# ESCapemk2.net
KiCad netlist of a schematic drawn in EAGLE
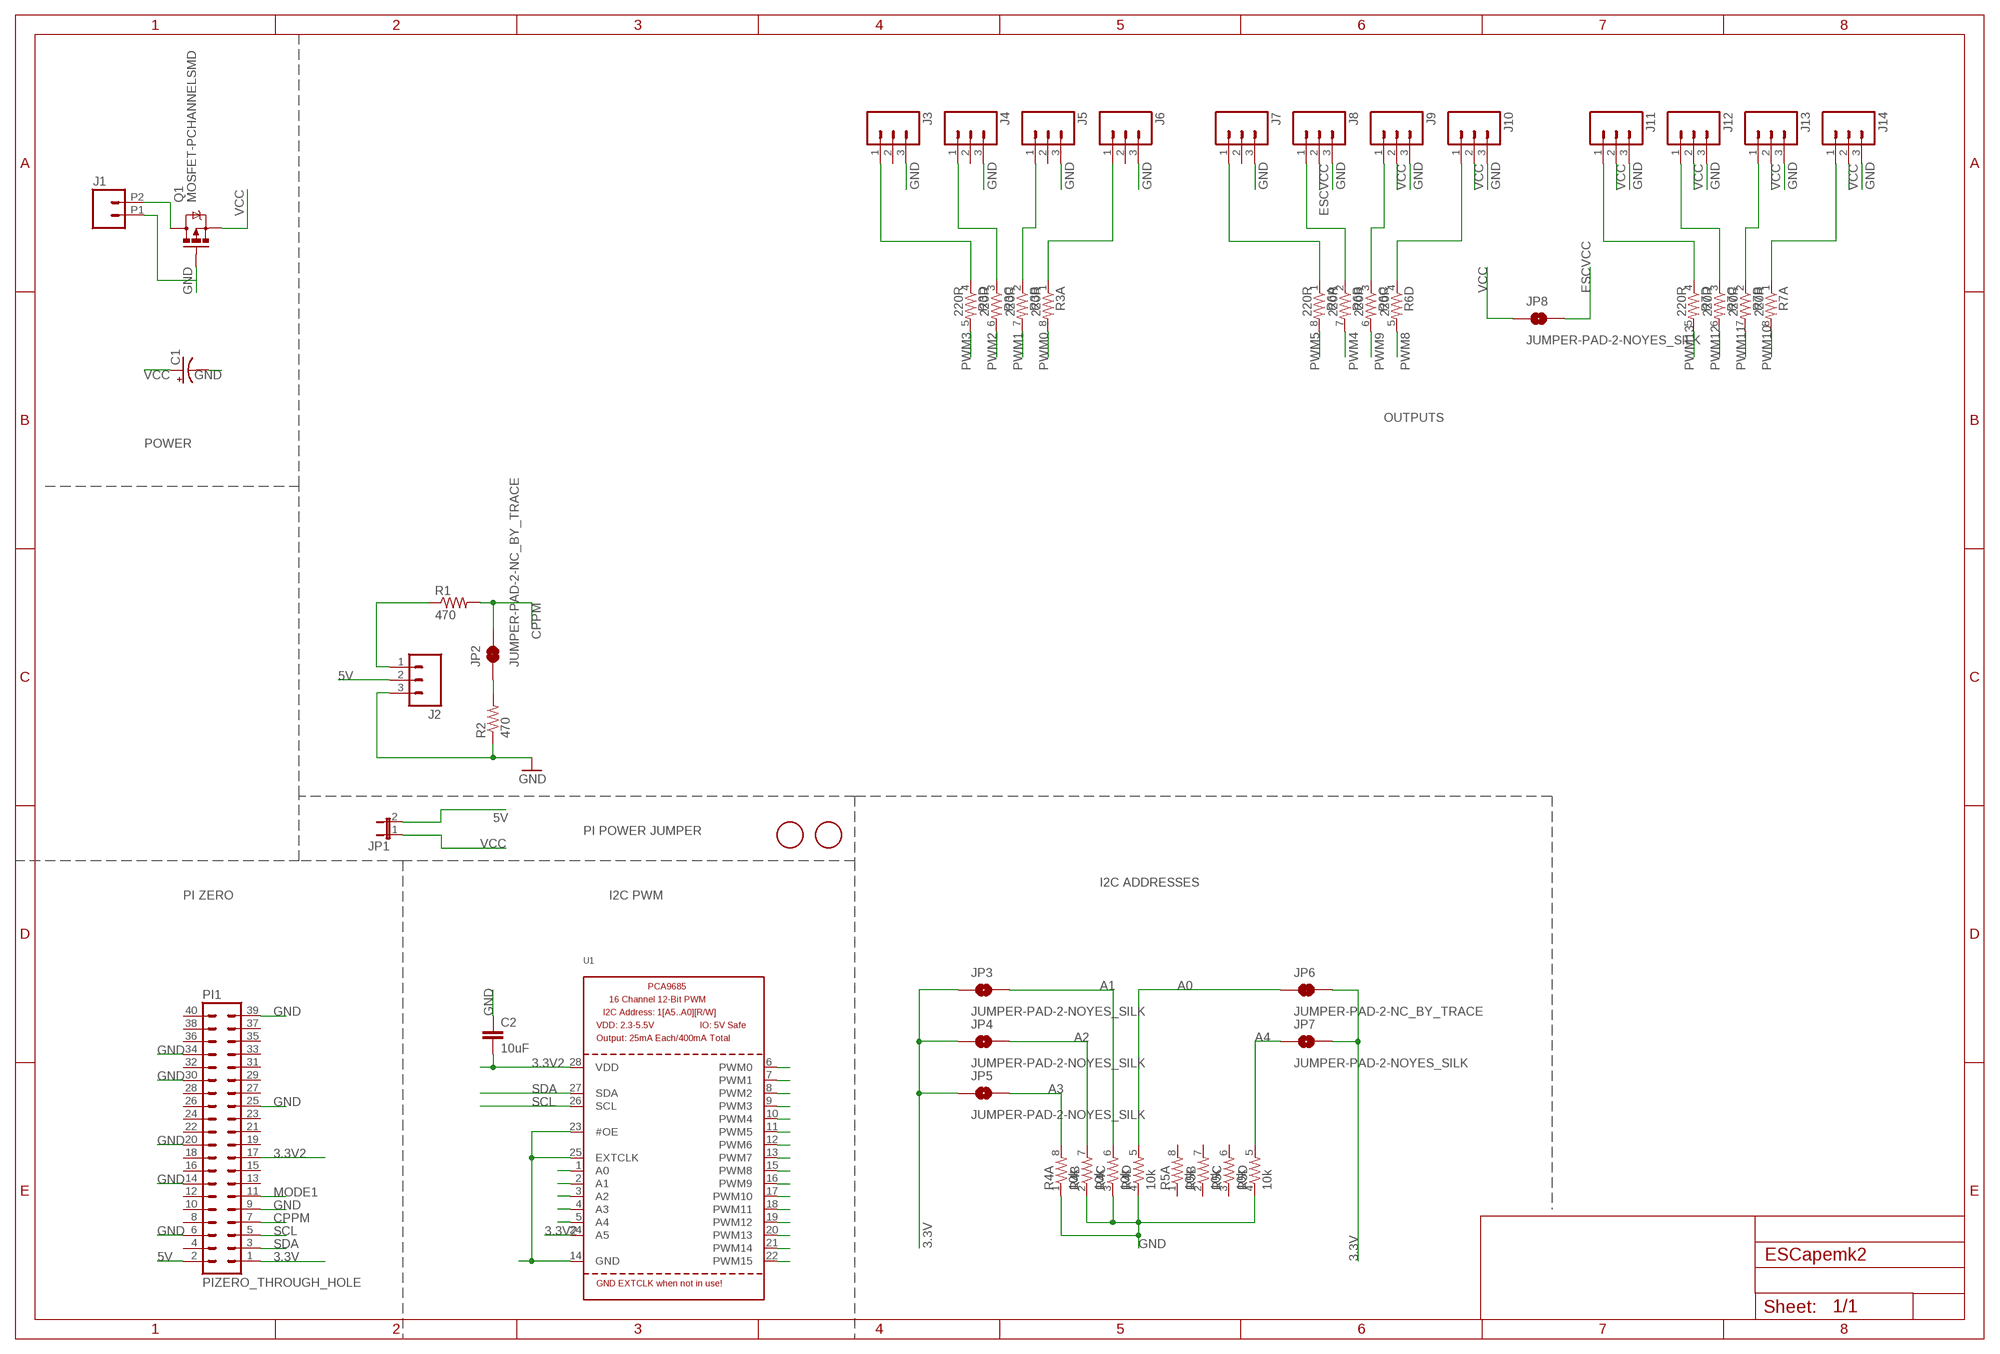
[diagram p0: schematic, sheet 1]

(export (version "E")
  (design (tool "Eeschema 10.0.6"))
  (components
    (comp (ref "C1")
      (value "CAP_POLPTH1")
      (footprint "eagle-import:CPOL-RADIAL-100UF-25V")
      (libsource (lib "eagle-import") (part "CAP_POLPTH1"))
    )
    (comp (ref "C2")
      (value "10uF")
      (footprint "eagle-import:0805")
      (libsource (lib "eagle-import") (part "CAP0805"))
    )
    (comp (ref "FID1")
      (value "FIDUCIAL")
      (footprint "eagle-import:FIDUCIAL_1MM")
      (libsource (lib "eagle-import") (part "FIDUCIAL"))
    )
    (comp (ref "FID2")
      (value "FIDUCIAL")
      (footprint "eagle-import:FIDUCIAL_1MM")
      (libsource (lib "eagle-import") (part "FIDUCIAL"))
    )
    (comp (ref "J1")
      (value "M022.54MM_SCREWTERM")
      (footprint "eagle-import:1X02_2.54_SCREWTERM")
      (libsource (lib "eagle-import") (part "M022.54MM_SCREWTERM"))
    )
    (comp (ref "J2")
      (value "M03LOCK")
      (footprint "eagle-import:1X03_LOCK")
      (libsource (lib "eagle-import") (part "M03LOCK"))
    )
    (comp (ref "J3")
      (value "M03LOCK")
      (footprint "eagle-import:1X03_LOCK")
      (libsource (lib "eagle-import") (part "M03LOCK"))
    )
    (comp (ref "J4")
      (value "M03LOCK")
      (footprint "eagle-import:1X03_LOCK")
      (libsource (lib "eagle-import") (part "M03LOCK"))
    )
    (comp (ref "J5")
      (value "M03LOCK")
      (footprint "eagle-import:1X03_LOCK")
      (libsource (lib "eagle-import") (part "M03LOCK"))
    )
    (comp (ref "J6")
      (value "M03LOCK")
      (footprint "eagle-import:1X03_LOCK")
      (libsource (lib "eagle-import") (part "M03LOCK"))
    )
    (comp (ref "J7")
      (value "M03LOCK")
      (footprint "eagle-import:1X03_LOCK")
      (libsource (lib "eagle-import") (part "M03LOCK"))
    )
    (comp (ref "J8")
      (value "M03LOCK")
      (footprint "eagle-import:1X03_LOCK")
      (libsource (lib "eagle-import") (part "M03LOCK"))
    )
    (comp (ref "J9")
      (value "M03LOCK")
      (footprint "eagle-import:1X03_LOCK")
      (libsource (lib "eagle-import") (part "M03LOCK"))
    )
    (comp (ref "J10")
      (value "M03LOCK")
      (footprint "eagle-import:1X03_LOCK")
      (libsource (lib "eagle-import") (part "M03LOCK"))
    )
    (comp (ref "J11")
      (value "M03LOCK")
      (footprint "eagle-import:1X03_LOCK")
      (libsource (lib "eagle-import") (part "M03LOCK"))
    )
    (comp (ref "J12")
      (value "M03LOCK")
      (footprint "eagle-import:1X03_LOCK")
      (libsource (lib "eagle-import") (part "M03LOCK"))
    )
    (comp (ref "J13")
      (value "M03LOCK")
      (footprint "eagle-import:1X03_LOCK")
      (libsource (lib "eagle-import") (part "M03LOCK"))
    )
    (comp (ref "J14")
      (value "M03LOCK")
      (footprint "eagle-import:1X03_LOCK")
      (libsource (lib "eagle-import") (part "M03LOCK"))
    )
    (comp (ref "JP1")
      (value "JUMPER-2PTH_LOCK")
      (footprint "eagle-import:1X02_LOCK")
      (libsource (lib "eagle-import") (part "JUMPER-2PTH_LOCK"))
    )
    (comp (ref "JP2")
      (value "JUMPER-PAD-2-NC_BY_TRACE")
      (footprint "eagle-import:PAD-JUMPER-2-NC_BY_TRACE_YES_SILK")
      (libsource (lib "eagle-import") (part "JUMPER-PAD-2-NC_BY_TRACE"))
    )
    (comp (ref "JP3")
      (value "JUMPER-PAD-2-NOYES_SILK")
      (footprint "eagle-import:PAD-JUMPER-2-NO_YES_SILK")
      (libsource (lib "eagle-import") (part "JUMPER-PAD-2-NOYES_SILK"))
    )
    (comp (ref "JP4")
      (value "JUMPER-PAD-2-NOYES_SILK")
      (footprint "eagle-import:PAD-JUMPER-2-NO_YES_SILK")
      (libsource (lib "eagle-import") (part "JUMPER-PAD-2-NOYES_SILK"))
    )
    (comp (ref "JP5")
      (value "JUMPER-PAD-2-NOYES_SILK")
      (footprint "eagle-import:PAD-JUMPER-2-NO_YES_SILK")
      (libsource (lib "eagle-import") (part "JUMPER-PAD-2-NOYES_SILK"))
    )
    (comp (ref "JP6")
      (value "JUMPER-PAD-2-NC_BY_TRACE")
      (footprint "eagle-import:PAD-JUMPER-2-NC_BY_TRACE_YES_SILK")
      (libsource (lib "eagle-import") (part "JUMPER-PAD-2-NC_BY_TRACE"))
    )
    (comp (ref "JP7")
      (value "JUMPER-PAD-2-NOYES_SILK")
      (footprint "eagle-import:PAD-JUMPER-2-NO_YES_SILK")
      (libsource (lib "eagle-import") (part "JUMPER-PAD-2-NOYES_SILK"))
    )
    (comp (ref "JP8")
      (value "JUMPER-PAD-2-NOYES_SILK")
      (footprint "eagle-import:PAD-JUMPER-2-NO_YES_SILK")
      (libsource (lib "eagle-import") (part "JUMPER-PAD-2-NOYES_SILK"))
    )
    (comp (ref "PI1")
      (value "PIZERO_THROUGH_HOLE")
      (footprint "eagle-import:PIZERO_THOUGH_HOLE")
      (libsource (lib "eagle-import") (part "PIZERO_THROUGH_HOLE"))
    )
    (comp (ref "Q1")
      (value "MOSFET-PCHANNELSMD")
      (footprint "eagle-import:SOT23-3")
      (libsource (lib "eagle-import") (part "MOSFET-PCHANNELSMD"))
    )
    (comp (ref "R1")
      (value "470")
      (footprint "eagle-import:0805")
      (libsource (lib "eagle-import") (part "RESISTOR0805-RES"))
    )
    (comp (ref "R2")
      (value "470")
      (footprint "eagle-import:0805")
      (libsource (lib "eagle-import") (part "RESISTOR0805-RES"))
    )
    (comp (ref "R3")
      (value "220R")
      (footprint "eagle-import:0603-ARV")
      (libsource (lib "eagle-import") (part "RESISTOR-ARRAY0603-ARV"))
    )
    (comp (ref "R4")
      (value "10k")
      (footprint "eagle-import:0603-ARV")
      (libsource (lib "eagle-import") (part "RESISTOR-ARRAY0603-ARV"))
    )
    (comp (ref "R5")
      (value "10k")
      (footprint "eagle-import:0603-ARV")
      (libsource (lib "eagle-import") (part "RESISTOR-ARRAY0603-ARV"))
    )
    (comp (ref "R6")
      (value "220R")
      (footprint "eagle-import:0603-ARV")
      (libsource (lib "eagle-import") (part "RESISTOR-ARRAY0603-ARV"))
    )
    (comp (ref "R7")
      (value "220R")
      (footprint "eagle-import:0603-ARV")
      (libsource (lib "eagle-import") (part "RESISTOR-ARRAY0603-ARV"))
    )
    (comp (ref "U1")
      (value "PCA9685")
      (footprint "eagle-import:TSSOP28")
      (libsource (lib "eagle-import") (part "PCA9685"))
    )
  )
  (nets
    (net (code "1") (name "/3.3V") (class "Default")
      (node (ref "JP3") (pin "1") (pinfunction "1_1") (pintype "passive"))
      (node (ref "JP4") (pin "1") (pinfunction "1_1") (pintype "passive"))
      (node (ref "JP5") (pin "1") (pinfunction "1_1") (pintype "passive"))
      (node (ref "JP6") (pin "2") (pinfunction "2_2") (pintype "passive"))
      (node (ref "JP7") (pin "2") (pinfunction "2_2") (pintype "passive"))
      (node (ref "PI1") (pin "1") (pinfunction "1_1") (pintype "passive"))
    )
    (net (code "2") (name "/3.3V2") (class "Default")
      (node (ref "C2") (pin "2") (pinfunction "2_2") (pintype "passive"))
      (node (ref "PI1") (pin "17") (pinfunction "17_17") (pintype "passive"))
      (node (ref "U1") (pin "24") (pinfunction "A5_24") (pintype "bidirectional"))
      (node (ref "U1") (pin "28") (pinfunction "VDD_28") (pintype "power_in"))
    )
    (net (code "3") (name "/5V") (class "Default")
      (node (ref "J2") (pin "2") (pinfunction "2_2") (pintype "passive"))
      (node (ref "JP1") (pin "2") (pinfunction "2_2") (pintype "passive"))
      (node (ref "PI1") (pin "2") (pinfunction "2_2") (pintype "passive"))
    )
    (net (code "4") (name "/A0") (class "Default")
      (node (ref "JP6") (pin "1") (pinfunction "1_1") (pintype "passive"))
      (node (ref "R4") (pin "5") (pinfunction "2_5") (pintype "passive"))
      (node (ref "U1") (pin "1") (pinfunction "A0_1") (pintype "bidirectional"))
    )
    (net (code "5") (name "/A1") (class "Default")
      (node (ref "JP3") (pin "2") (pinfunction "2_2") (pintype "passive"))
      (node (ref "R4") (pin "6") (pinfunction "2_6") (pintype "passive"))
      (node (ref "U1") (pin "2") (pinfunction "A1_2") (pintype "bidirectional"))
    )
    (net (code "6") (name "/A2") (class "Default")
      (node (ref "JP4") (pin "2") (pinfunction "2_2") (pintype "passive"))
      (node (ref "R4") (pin "7") (pinfunction "2_7") (pintype "passive"))
      (node (ref "U1") (pin "3") (pinfunction "A2_3") (pintype "bidirectional"))
    )
    (net (code "7") (name "/A3") (class "Default")
      (node (ref "JP5") (pin "2") (pinfunction "2_2") (pintype "passive"))
      (node (ref "R4") (pin "8") (pinfunction "2_8") (pintype "passive"))
      (node (ref "U1") (pin "4") (pinfunction "A3_4") (pintype "bidirectional"))
    )
    (net (code "8") (name "/A4") (class "Default")
      (node (ref "JP7") (pin "1") (pinfunction "1_1") (pintype "passive"))
      (node (ref "R5") (pin "5") (pinfunction "2_5") (pintype "passive"))
      (node (ref "U1") (pin "5") (pinfunction "A4_5") (pintype "bidirectional"))
    )
    (net (code "9") (name "/CPPM") (class "Default")
      (node (ref "JP2") (pin "2") (pinfunction "2_2") (pintype "passive"))
      (node (ref "PI1") (pin "7") (pinfunction "7_7") (pintype "passive"))
      (node (ref "R1") (pin "2") (pinfunction "2_2") (pintype "passive"))
    )
    (net (code "10") (name "/ESCVCC") (class "Default")
      (node (ref "J8") (pin "2") (pinfunction "2_2") (pintype "passive"))
      (node (ref "JP8") (pin "2") (pinfunction "2_2") (pintype "passive"))
    )
    (net (code "11") (name "/MODE1") (class "Default")
      (node (ref "PI1") (pin "11") (pinfunction "11_11") (pintype "passive"))
    )
    (net (code "12") (name "/PWM0") (class "Default")
      (node (ref "R3") (pin "8") (pinfunction "2_8") (pintype "passive"))
      (node (ref "U1") (pin "6") (pinfunction "PWM0_6") (pintype "output"))
    )
    (net (code "13") (name "/PWM1") (class "Default")
      (node (ref "R3") (pin "7") (pinfunction "2_7") (pintype "passive"))
      (node (ref "U1") (pin "7") (pinfunction "PWM1_7") (pintype "output"))
    )
    (net (code "14") (name "/PWM2") (class "Default")
      (node (ref "R3") (pin "6") (pinfunction "2_6") (pintype "passive"))
      (node (ref "U1") (pin "8") (pinfunction "PWM2_8") (pintype "output"))
    )
    (net (code "15") (name "/PWM3") (class "Default")
      (node (ref "R3") (pin "5") (pinfunction "2_5") (pintype "passive"))
      (node (ref "U1") (pin "9") (pinfunction "PWM3_9") (pintype "output"))
    )
    (net (code "16") (name "/PWM4") (class "Default")
      (node (ref "R6") (pin "7") (pinfunction "2_7") (pintype "passive"))
      (node (ref "U1") (pin "10") (pinfunction "PWM4_10") (pintype "output"))
    )
    (net (code "17") (name "/PWM5") (class "Default")
      (node (ref "R6") (pin "8") (pinfunction "2_8") (pintype "passive"))
      (node (ref "U1") (pin "11") (pinfunction "PWM5_11") (pintype "output"))
    )
    (net (code "18") (name "/PWM8") (class "Default")
      (node (ref "R6") (pin "5") (pinfunction "2_5") (pintype "passive"))
      (node (ref "U1") (pin "15") (pinfunction "PWM8_15") (pintype "output"))
    )
    (net (code "19") (name "/PWM9") (class "Default")
      (node (ref "R6") (pin "6") (pinfunction "2_6") (pintype "passive"))
      (node (ref "U1") (pin "16") (pinfunction "PWM9_16") (pintype "output"))
    )
    (net (code "20") (name "/PWM10") (class "Default")
      (node (ref "R7") (pin "8") (pinfunction "2_8") (pintype "passive"))
      (node (ref "U1") (pin "17") (pinfunction "PWM10_17") (pintype "output"))
    )
    (net (code "21") (name "/PWM11") (class "Default")
      (node (ref "R7") (pin "7") (pinfunction "2_7") (pintype "passive"))
      (node (ref "U1") (pin "18") (pinfunction "PWM11_18") (pintype "output"))
    )
    (net (code "22") (name "/PWM12") (class "Default")
      (node (ref "R7") (pin "6") (pinfunction "2_6") (pintype "passive"))
      (node (ref "U1") (pin "19") (pinfunction "PWM12_19") (pintype "output"))
    )
    (net (code "23") (name "/PWM13") (class "Default")
      (node (ref "R7") (pin "5") (pinfunction "2_5") (pintype "passive"))
      (node (ref "U1") (pin "20") (pinfunction "PWM13_20") (pintype "output"))
    )
    (net (code "24") (name "/SCL") (class "Default")
      (node (ref "PI1") (pin "5") (pinfunction "5_5") (pintype "passive"))
      (node (ref "U1") (pin "26") (pinfunction "SCL_26") (pintype "bidirectional"))
    )
    (net (code "25") (name "/SDA") (class "Default")
      (node (ref "PI1") (pin "3") (pinfunction "3_3") (pintype "passive"))
      (node (ref "U1") (pin "27") (pinfunction "SDA_27") (pintype "bidirectional"))
    )
    (net (code "26") (name "/VCC") (class "Default")
      (node (ref "C1") (pin "1") (pinfunction "+_1") (pintype "passive"))
      (node (ref "J10") (pin "2") (pinfunction "2_2") (pintype "passive"))
      (node (ref "J11") (pin "2") (pinfunction "2_2") (pintype "passive"))
      (node (ref "J12") (pin "2") (pinfunction "2_2") (pintype "passive"))
      (node (ref "J13") (pin "2") (pinfunction "2_2") (pintype "passive"))
      (node (ref "J14") (pin "2") (pinfunction "2_2") (pintype "passive"))
      (node (ref "J9") (pin "2") (pinfunction "2_2") (pintype "passive"))
      (node (ref "JP1") (pin "1") (pinfunction "1_1") (pintype "passive"))
      (node (ref "JP8") (pin "1") (pinfunction "1_1") (pintype "passive"))
      (node (ref "Q1") (pin "2") (pinfunction "S_2") (pintype "passive"))
    )
    (net (code "27") (name "GND") (class "Default")
      (node (ref "C1") (pin "2") (pinfunction "-_2") (pintype "passive"))
      (node (ref "C2") (pin "1") (pinfunction "1_1") (pintype "passive"))
      (node (ref "J1") (pin "P1") (pinfunction "1_P1") (pintype "passive"))
      (node (ref "J10") (pin "3") (pinfunction "3_3") (pintype "passive"))
      (node (ref "J11") (pin "3") (pinfunction "3_3") (pintype "passive"))
      (node (ref "J12") (pin "3") (pinfunction "3_3") (pintype "passive"))
      (node (ref "J13") (pin "3") (pinfunction "3_3") (pintype "passive"))
      (node (ref "J14") (pin "3") (pinfunction "3_3") (pintype "passive"))
      (node (ref "J2") (pin "3") (pinfunction "3_3") (pintype "passive"))
      (node (ref "J3") (pin "3") (pinfunction "3_3") (pintype "passive"))
      (node (ref "J4") (pin "3") (pinfunction "3_3") (pintype "passive"))
      (node (ref "J5") (pin "3") (pinfunction "3_3") (pintype "passive"))
      (node (ref "J6") (pin "3") (pinfunction "3_3") (pintype "passive"))
      (node (ref "J7") (pin "3") (pinfunction "3_3") (pintype "passive"))
      (node (ref "J8") (pin "3") (pinfunction "3_3") (pintype "passive"))
      (node (ref "J9") (pin "3") (pinfunction "3_3") (pintype "passive"))
      (node (ref "PI1") (pin "14") (pinfunction "14_14") (pintype "passive"))
      (node (ref "PI1") (pin "20") (pinfunction "20_20") (pintype "passive"))
      (node (ref "PI1") (pin "25") (pinfunction "25_25") (pintype "passive"))
      (node (ref "PI1") (pin "30") (pinfunction "30_30") (pintype "passive"))
      (node (ref "PI1") (pin "34") (pinfunction "34_34") (pintype "passive"))
      (node (ref "PI1") (pin "39") (pinfunction "39_39") (pintype "passive"))
      (node (ref "PI1") (pin "6") (pinfunction "6_6") (pintype "passive"))
      (node (ref "PI1") (pin "9") (pinfunction "9_9") (pintype "passive"))
      (node (ref "Q1") (pin "1") (pinfunction "G_1") (pintype "passive"))
      (node (ref "R2") (pin "1") (pinfunction "1_1") (pintype "passive"))
      (node (ref "R4") (pin "1") (pinfunction "1_1") (pintype "passive"))
      (node (ref "R4") (pin "2") (pinfunction "1_2") (pintype "passive"))
      (node (ref "R4") (pin "3") (pinfunction "1_3") (pintype "passive"))
      (node (ref "R4") (pin "4") (pinfunction "1_4") (pintype "passive"))
      (node (ref "R5") (pin "4") (pinfunction "1_4") (pintype "passive"))
      (node (ref "U1") (pin "14") (pinfunction "GND_14") (pintype "power_in"))
      (node (ref "U1") (pin "23") (pinfunction "#OE_23") (pintype "input"))
      (node (ref "U1") (pin "25") (pinfunction "EXTCLK_25") (pintype "input"))
    )
    (net (code "28") (name "Net-(J1-2)") (class "Default")
      (node (ref "J1") (pin "P2") (pinfunction "2_P2") (pintype "passive"))
      (node (ref "Q1") (pin "3") (pinfunction "D_3") (pintype "passive"))
    )
    (net (code "29") (name "Net-(J2-Pad1)") (class "Default")
      (node (ref "J2") (pin "1") (pinfunction "1_1") (pintype "passive"))
      (node (ref "R1") (pin "1") (pinfunction "1_1") (pintype "passive"))
    )
    (net (code "30") (name "Net-(J6-Pad1)") (class "Default")
      (node (ref "J6") (pin "1") (pinfunction "1_1") (pintype "passive"))
      (node (ref "R3") (pin "1") (pinfunction "1_1") (pintype "passive"))
    )
    (net (code "31") (name "Net-(J7-Pad1)") (class "Default")
      (node (ref "J7") (pin "1") (pinfunction "1_1") (pintype "passive"))
      (node (ref "R6") (pin "1") (pinfunction "1_1") (pintype "passive"))
    )
    (net (code "32") (name "Net-(J14-Pad1)") (class "Default")
      (node (ref "J14") (pin "1") (pinfunction "1_1") (pintype "passive"))
      (node (ref "R7") (pin "1") (pinfunction "1_1") (pintype "passive"))
    )
    (net (code "33") (name "Net-(JP2-Pad1)") (class "Default")
      (node (ref "JP2") (pin "1") (pinfunction "1_1") (pintype "passive"))
      (node (ref "R2") (pin "2") (pinfunction "2_2") (pintype "passive"))
    )
    (net (code "34") (name "Net-(R3B-1)") (class "Default")
      (node (ref "J5") (pin "1") (pinfunction "1_1") (pintype "passive"))
      (node (ref "R3") (pin "2") (pinfunction "1_2") (pintype "passive"))
    )
    (net (code "35") (name "Net-(R3C-1)") (class "Default")
      (node (ref "J4") (pin "1") (pinfunction "1_1") (pintype "passive"))
      (node (ref "R3") (pin "3") (pinfunction "1_3") (pintype "passive"))
    )
    (net (code "36") (name "Net-(R3D-1)") (class "Default")
      (node (ref "J3") (pin "1") (pinfunction "1_1") (pintype "passive"))
      (node (ref "R3") (pin "4") (pinfunction "1_4") (pintype "passive"))
    )
    (net (code "37") (name "Net-(R6B-1)") (class "Default")
      (node (ref "J8") (pin "1") (pinfunction "1_1") (pintype "passive"))
      (node (ref "R6") (pin "2") (pinfunction "1_2") (pintype "passive"))
    )
    (net (code "38") (name "Net-(R6C-1)") (class "Default")
      (node (ref "J9") (pin "1") (pinfunction "1_1") (pintype "passive"))
      (node (ref "R6") (pin "3") (pinfunction "1_3") (pintype "passive"))
    )
    (net (code "39") (name "Net-(R6D-1)") (class "Default")
      (node (ref "J10") (pin "1") (pinfunction "1_1") (pintype "passive"))
      (node (ref "R6") (pin "4") (pinfunction "1_4") (pintype "passive"))
    )
    (net (code "40") (name "Net-(R7B-1)") (class "Default")
      (node (ref "J13") (pin "1") (pinfunction "1_1") (pintype "passive"))
      (node (ref "R7") (pin "2") (pinfunction "1_2") (pintype "passive"))
    )
    (net (code "41") (name "Net-(R7C-1)") (class "Default")
      (node (ref "J12") (pin "1") (pinfunction "1_1") (pintype "passive"))
      (node (ref "R7") (pin "3") (pinfunction "1_3") (pintype "passive"))
    )
    (net (code "42") (name "Net-(R7D-1)") (class "Default")
      (node (ref "J11") (pin "1") (pinfunction "1_1") (pintype "passive"))
      (node (ref "R7") (pin "4") (pinfunction "1_4") (pintype "passive"))
    )
    (net (code "43") (name "unconnected-(J3-Pad2)") (class "Default")
      (node (ref "J3") (pin "2") (pinfunction "2_2") (pintype "passive"))
    )
    (net (code "44") (name "unconnected-(J4-Pad2)") (class "Default")
      (node (ref "J4") (pin "2") (pinfunction "2_2") (pintype "passive"))
    )
    (net (code "45") (name "unconnected-(J5-Pad2)") (class "Default")
      (node (ref "J5") (pin "2") (pinfunction "2_2") (pintype "passive"))
    )
    (net (code "46") (name "unconnected-(J6-Pad2)") (class "Default")
      (node (ref "J6") (pin "2") (pinfunction "2_2") (pintype "passive"))
    )
    (net (code "47") (name "unconnected-(J7-Pad2)") (class "Default")
      (node (ref "J7") (pin "2") (pinfunction "2_2") (pintype "passive"))
    )
    (net (code "48") (name "unconnected-(PI1-Pad4)") (class "Default")
      (node (ref "PI1") (pin "4") (pinfunction "4_4") (pintype "passive"))
    )
    (net (code "49") (name "unconnected-(PI1-Pad8)") (class "Default")
      (node (ref "PI1") (pin "8") (pinfunction "8_8") (pintype "passive"))
    )
    (net (code "50") (name "unconnected-(PI1-Pad10)") (class "Default")
      (node (ref "PI1") (pin "10") (pinfunction "10_10") (pintype "passive"))
    )
    (net (code "51") (name "unconnected-(PI1-Pad12)") (class "Default")
      (node (ref "PI1") (pin "12") (pinfunction "12_12") (pintype "passive"))
    )
    (net (code "52") (name "unconnected-(PI1-Pad13)") (class "Default")
      (node (ref "PI1") (pin "13") (pinfunction "13_13") (pintype "passive"))
    )
    (net (code "53") (name "unconnected-(PI1-Pad15)") (class "Default")
      (node (ref "PI1") (pin "15") (pinfunction "15_15") (pintype "passive"))
    )
    (net (code "54") (name "unconnected-(PI1-Pad16)") (class "Default")
      (node (ref "PI1") (pin "16") (pinfunction "16_16") (pintype "passive"))
    )
    (net (code "55") (name "unconnected-(PI1-Pad18)") (class "Default")
      (node (ref "PI1") (pin "18") (pinfunction "18_18") (pintype "passive"))
    )
    (net (code "56") (name "unconnected-(PI1-Pad19)") (class "Default")
      (node (ref "PI1") (pin "19") (pinfunction "19_19") (pintype "passive"))
    )
    (net (code "57") (name "unconnected-(PI1-Pad21)") (class "Default")
      (node (ref "PI1") (pin "21") (pinfunction "21_21") (pintype "passive"))
    )
    (net (code "58") (name "unconnected-(PI1-Pad22)") (class "Default")
      (node (ref "PI1") (pin "22") (pinfunction "22_22") (pintype "passive"))
    )
    (net (code "59") (name "unconnected-(PI1-Pad23)") (class "Default")
      (node (ref "PI1") (pin "23") (pinfunction "23_23") (pintype "passive"))
    )
    (net (code "60") (name "unconnected-(PI1-Pad24)") (class "Default")
      (node (ref "PI1") (pin "24") (pinfunction "24_24") (pintype "passive"))
    )
    (net (code "61") (name "unconnected-(PI1-Pad26)") (class "Default")
      (node (ref "PI1") (pin "26") (pinfunction "26_26") (pintype "passive"))
    )
    (net (code "62") (name "unconnected-(PI1-Pad27)") (class "Default")
      (node (ref "PI1") (pin "27") (pinfunction "27_27") (pintype "passive"))
    )
    (net (code "63") (name "unconnected-(PI1-Pad28)") (class "Default")
      (node (ref "PI1") (pin "28") (pinfunction "28_28") (pintype "passive"))
    )
    (net (code "64") (name "unconnected-(PI1-Pad29)") (class "Default")
      (node (ref "PI1") (pin "29") (pinfunction "29_29") (pintype "passive"))
    )
    (net (code "65") (name "unconnected-(PI1-Pad31)") (class "Default")
      (node (ref "PI1") (pin "31") (pinfunction "31_31") (pintype "passive"))
    )
    (net (code "66") (name "unconnected-(PI1-Pad32)") (class "Default")
      (node (ref "PI1") (pin "32") (pinfunction "32_32") (pintype "passive"))
    )
    (net (code "67") (name "unconnected-(PI1-Pad33)") (class "Default")
      (node (ref "PI1") (pin "33") (pinfunction "33_33") (pintype "passive"))
    )
    (net (code "68") (name "unconnected-(PI1-Pad35)") (class "Default")
      (node (ref "PI1") (pin "35") (pinfunction "35_35") (pintype "passive"))
    )
    (net (code "69") (name "unconnected-(PI1-Pad36)") (class "Default")
      (node (ref "PI1") (pin "36") (pinfunction "36_36") (pintype "passive"))
    )
    (net (code "70") (name "unconnected-(PI1-Pad37)") (class "Default")
      (node (ref "PI1") (pin "37") (pinfunction "37_37") (pintype "passive"))
    )
    (net (code "71") (name "unconnected-(PI1-Pad38)") (class "Default")
      (node (ref "PI1") (pin "38") (pinfunction "38_38") (pintype "passive"))
    )
    (net (code "72") (name "unconnected-(PI1-Pad40)") (class "Default")
      (node (ref "PI1") (pin "40") (pinfunction "40_40") (pintype "passive"))
    )
    (net (code "73") (name "unconnected-(R5-Pad1)") (class "Default")
      (node (ref "R5") (pin "1") (pinfunction "1_1") (pintype "passive"))
    )
    (net (code "74") (name "unconnected-(R5A-2-Pad8)") (class "Default")
      (node (ref "R5") (pin "8") (pinfunction "2_8") (pintype "passive"))
    )
    (net (code "75") (name "unconnected-(R5B-1-Pad2)") (class "Default")
      (node (ref "R5") (pin "2") (pinfunction "1_2") (pintype "passive"))
    )
    (net (code "76") (name "unconnected-(R5B-2-Pad7)") (class "Default")
      (node (ref "R5") (pin "7") (pinfunction "2_7") (pintype "passive"))
    )
    (net (code "77") (name "unconnected-(R5C-1-Pad3)") (class "Default")
      (node (ref "R5") (pin "3") (pinfunction "1_3") (pintype "passive"))
    )
    (net (code "78") (name "unconnected-(R5C-2-Pad6)") (class "Default")
      (node (ref "R5") (pin "6") (pinfunction "2_6") (pintype "passive"))
    )
    (net (code "79") (name "unconnected-(U1-PWM6-Pad12)") (class "Default")
      (node (ref "U1") (pin "12") (pinfunction "PWM6_12") (pintype "output"))
    )
    (net (code "80") (name "unconnected-(U1-PWM7-Pad13)") (class "Default")
      (node (ref "U1") (pin "13") (pinfunction "PWM7_13") (pintype "output"))
    )
    (net (code "81") (name "unconnected-(U1-PWM14-Pad21)") (class "Default")
      (node (ref "U1") (pin "21") (pinfunction "PWM14_21") (pintype "output"))
    )
    (net (code "82") (name "unconnected-(U1-PWM15-Pad22)") (class "Default")
      (node (ref "U1") (pin "22") (pinfunction "PWM15_22") (pintype "output"))
    )
  )
)
